# lcd.net
KiCad netlist of a schematic drawn in Altium Designer
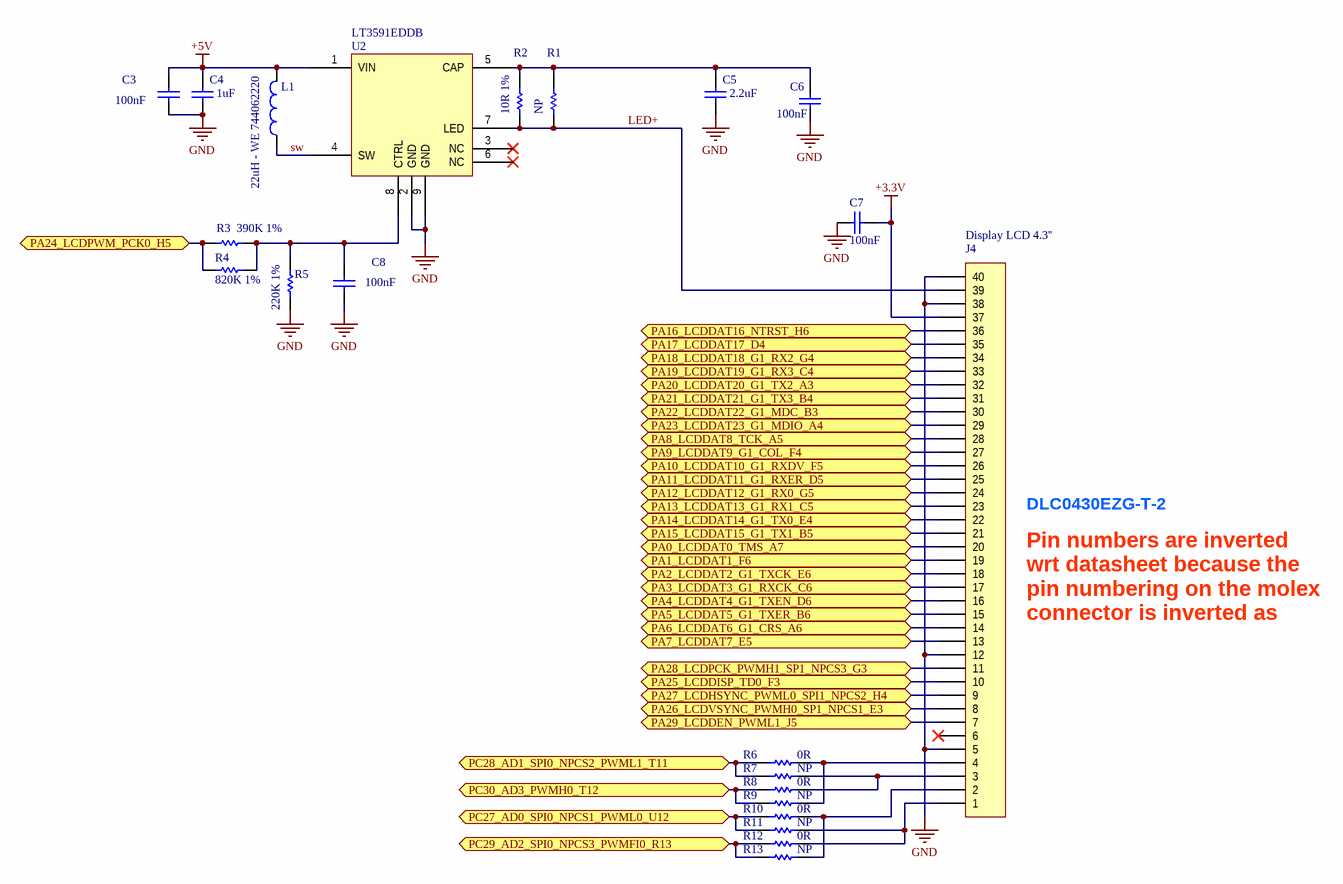
[diagram p0: lcd.SchDoc]

(export (version "E")
  (design (tool "Eeschema 10.0.6"))
  (components
    (comp (ref "C3")
      (value "100nF")
      (footprint "0603_[1608]")
      (description "Ceramic X7R 50V")
      (fields (field (name "PUBLISHER") "Altium Limited"))
      (libsource (lib "project42_lib") (part "Cap"))
    )
    (comp (ref "C4")
      (value "1uF")
      (footprint "0603_[1608]")
      (description "Ceramic X7R, X5R 16V")
      (fields (field (name "PUBLISHER") "Altium Limited"))
      (libsource (lib "project42_lib") (part "Cap"))
    )
    (comp (ref "C5")
      (value "2.2uF")
      (footprint "1210_[3225]")
      (description "Ceramic X7R, X5R 50V")
      (fields (field (name "PUBLISHER") "Altium Limited"))
      (libsource (lib "project42_lib") (part "Cap"))
    )
    (comp (ref "C6")
      (value "100nF")
      (footprint "0603_[1608]")
      (description "Ceramic X7R 50V")
      (fields (field (name "PUBLISHER") "Altium Limited"))
      (libsource (lib "project42_lib") (part "Cap"))
    )
    (comp (ref "C7")
      (value "100nF")
      (footprint "0603_[1608]")
      (description "Ceramic X5R 6.3V, 10V")
      (fields (field (name "PUBLISHER") "Altium Limited"))
      (libsource (lib "project42_lib") (part "Cap"))
    )
    (comp (ref "C8")
      (value "100nF")
      (footprint "0603_[1608]")
      (description "Ceramic X7R 50V")
      (fields (field (name "PUBLISHER") "Altium Limited"))
      (libsource (lib "project42_lib") (part "Cap"))
    )
    (comp (ref "J4")
      (value "Display LCD 4.3''")
      (footprint "fcc-zif_40pin_0.5mm")
      (description "40-pin, 0.5mm, SMT, ZIF, Horizontal, Top Contact (WE 68714014022; Molex: 54104-4031)")
      (fields (field (name "PUBLISHER") "Altium Limited"))
      (libsource (lib "DEVELER_Library") (part "Header 40"))
    )
    (comp (ref "L1")
      (value "22uH - WE 744062220")
      (footprint "WE-TPC-6823-X")
      (description "Power Inductor")
      (libsource (lib "DEVELER_Library") (part "Inductor"))
    )
    (comp (ref "R1")
      (value "NP")
      (footprint "0603_[1608]")
      (description "Resistor 0.125W")
      (fields (field (name "PUBLISHER") "Altium Limited"))
      (libsource (lib "project42_lib") (part "Res1"))
    )
    (comp (ref "R2")
      (value "10R 1%")
      (footprint "0603_[1608]")
      (description "Resistor 0.125W")
      (fields (field (name "PUBLISHER") "Altium Limited"))
      (libsource (lib "project42_lib") (part "Res1"))
    )
    (comp (ref "R3")
      (value "390K 1%")
      (footprint "0603_[1608]")
      (description "Resistor")
      (fields (field (name "PUBLISHER") "Altium Limited"))
      (libsource (lib "project42_lib") (part "Res1"))
    )
    (comp (ref "R4")
      (value "820K 1%")
      (footprint "0603_[1608]")
      (description "Resistor")
      (fields (field (name "PUBLISHER") "Altium Limited"))
      (libsource (lib "project42_lib") (part "Res1"))
    )
    (comp (ref "R5")
      (value "220K 1%")
      (footprint "0603_[1608]")
      (description "Resistor")
      (fields (field (name "PUBLISHER") "Altium Limited"))
      (libsource (lib "project42_lib") (part "Res1"))
    )
    (comp (ref "R6")
      (value "0R")
      (footprint "0603_[1608]")
      (description "Resistor")
      (fields (field (name "PUBLISHER") "Altium Limited"))
      (libsource (lib "project42_lib") (part "Res1"))
    )
    (comp (ref "R7")
      (value "NP")
      (footprint "0603_[1608]")
      (description "Resistor")
      (fields (field (name "PUBLISHER") "Altium Limited"))
      (libsource (lib "project42_lib") (part "Res1"))
    )
    (comp (ref "R8")
      (value "0R")
      (footprint "0603_[1608]")
      (description "Resistor")
      (fields (field (name "PUBLISHER") "Altium Limited"))
      (libsource (lib "project42_lib") (part "Res1"))
    )
    (comp (ref "R9")
      (value "NP")
      (footprint "0603_[1608]")
      (description "Resistor")
      (fields (field (name "PUBLISHER") "Altium Limited"))
      (libsource (lib "project42_lib") (part "Res1"))
    )
    (comp (ref "R10")
      (value "0R")
      (footprint "0603_[1608]")
      (description "Resistor")
      (fields (field (name "PUBLISHER") "Altium Limited"))
      (libsource (lib "project42_lib") (part "Res1"))
    )
    (comp (ref "R11")
      (value "NP")
      (footprint "0603_[1608]")
      (description "Resistor")
      (fields (field (name "PUBLISHER") "Altium Limited"))
      (libsource (lib "project42_lib") (part "Res1"))
    )
    (comp (ref "R12")
      (value "0R")
      (footprint "0603_[1608]")
      (description "Resistor")
      (fields (field (name "PUBLISHER") "Altium Limited"))
      (libsource (lib "project42_lib") (part "Res1"))
    )
    (comp (ref "R13")
      (value "NP")
      (footprint "0603_[1608]")
      (description "Resistor")
      (fields (field (name "PUBLISHER") "Altium Limited"))
      (libsource (lib "project42_lib") (part "Res1"))
    )
    (comp (ref "U2")
      (value "LT3591EDDB")
      (footprint "PQFN50P300X200X75_HS-9L")
      (description "White LED Driver with Integrated Schottky")
      (libsource (lib "DEVELER_Library") (part "LT3591"))
    )
  )
  (nets
    (net (code "1") (name "+3.3V") (class "Default")
      (node (ref "C7") (pin "1") (pinfunction "1_1") (pintype "passive"))
      (node (ref "J4") (pin "37") (pinfunction "37_37") (pintype "passive"))
    )
    (net (code "2") (name "+5V") (class "Default")
      (node (ref "C3") (pin "2") (pinfunction "2_2") (pintype "passive"))
      (node (ref "C4") (pin "2") (pinfunction "2_2") (pintype "passive"))
      (node (ref "L1") (pin "2") (pinfunction "2_2") (pintype "passive"))
      (node (ref "U2") (pin "1") (pinfunction "VIN_1") (pintype "power_in"))
    )
    (net (code "3") (name "/LED+") (class "Default")
      (node (ref "J4") (pin "39") (pinfunction "39_39") (pintype "passive"))
      (node (ref "R1") (pin "1") (pinfunction "1_1") (pintype "passive"))
      (node (ref "R2") (pin "1") (pinfunction "1_1") (pintype "passive"))
      (node (ref "U2") (pin "7") (pinfunction "LED_7") (pintype "passive"))
    )
    (net (code "4") (name "/PA0_LCDDAT0_TMS_A7") (class "Default")
      (node (ref "J4") (pin "20") (pinfunction "20_20") (pintype "passive"))
    )
    (net (code "5") (name "/PA1_LCDDAT1_F6") (class "Default")
      (node (ref "J4") (pin "19") (pinfunction "19_19") (pintype "passive"))
    )
    (net (code "6") (name "/PA2_LCDDAT2_G1_TXCK_E6") (class "Default")
      (node (ref "J4") (pin "18") (pinfunction "18_18") (pintype "passive"))
    )
    (net (code "7") (name "/PA3_LCDDAT3_G1_RXCK_C6") (class "Default")
      (node (ref "J4") (pin "17") (pinfunction "17_17") (pintype "passive"))
    )
    (net (code "8") (name "/PA4_LCDDAT4_G1_TXEN_D6") (class "Default")
      (node (ref "J4") (pin "16") (pinfunction "16_16") (pintype "passive"))
    )
    (net (code "9") (name "/PA5_LCDDAT5_G1_TXER_B6") (class "Default")
      (node (ref "J4") (pin "15") (pinfunction "15_15") (pintype "passive"))
    )
    (net (code "10") (name "/PA6_LCDDAT6_G1_CRS_A6") (class "Default")
      (node (ref "J4") (pin "14") (pinfunction "14_14") (pintype "passive"))
    )
    (net (code "11") (name "/PA7_LCDDAT7_E5") (class "Default")
      (node (ref "J4") (pin "13") (pinfunction "13_13") (pintype "passive"))
    )
    (net (code "12") (name "/PA8_LCDDAT8_TCK_A5") (class "Default")
      (node (ref "J4") (pin "28") (pinfunction "28_28") (pintype "passive"))
    )
    (net (code "13") (name "/PA9_LCDDAT9_G1_COL_F4") (class "Default")
      (node (ref "J4") (pin "27") (pinfunction "27_27") (pintype "passive"))
    )
    (net (code "14") (name "/PA10_LCDDAT10_G1_RXDV_F5") (class "Default")
      (node (ref "J4") (pin "26") (pinfunction "26_26") (pintype "passive"))
    )
    (net (code "15") (name "/PA11_LCDDAT11_G1_RXER_D5") (class "Default")
      (node (ref "J4") (pin "25") (pinfunction "25_25") (pintype "passive"))
    )
    (net (code "16") (name "/PA12_LCDDAT12_G1_RX0_G5") (class "Default")
      (node (ref "J4") (pin "24") (pinfunction "24_24") (pintype "passive"))
    )
    (net (code "17") (name "/PA13_LCDDAT13_G1_RX1_C5") (class "Default")
      (node (ref "J4") (pin "23") (pinfunction "23_23") (pintype "passive"))
    )
    (net (code "18") (name "/PA14_LCDDAT14_G1_TX0_E4") (class "Default")
      (node (ref "J4") (pin "22") (pinfunction "22_22") (pintype "passive"))
    )
    (net (code "19") (name "/PA15_LCDDAT15_G1_TX1_B5") (class "Default")
      (node (ref "J4") (pin "21") (pinfunction "21_21") (pintype "passive"))
    )
    (net (code "20") (name "/PA16_LCDDAT16_NTRST_H6") (class "Default")
      (node (ref "J4") (pin "36") (pinfunction "36_36") (pintype "passive"))
    )
    (net (code "21") (name "/PA17_LCDDAT17_D4") (class "Default")
      (node (ref "J4") (pin "35") (pinfunction "35_35") (pintype "passive"))
    )
    (net (code "22") (name "/PA18_LCDDAT18_G1_RX2_G4") (class "Default")
      (node (ref "J4") (pin "34") (pinfunction "34_34") (pintype "passive"))
    )
    (net (code "23") (name "/PA19_LCDDAT19_G1_RX3_C4") (class "Default")
      (node (ref "J4") (pin "33") (pinfunction "33_33") (pintype "passive"))
    )
    (net (code "24") (name "/PA20_LCDDAT20_G1_TX2_A3") (class "Default")
      (node (ref "J4") (pin "32") (pinfunction "32_32") (pintype "passive"))
    )
    (net (code "25") (name "/PA21_LCDDAT21_G1_TX3_B4") (class "Default")
      (node (ref "J4") (pin "31") (pinfunction "31_31") (pintype "passive"))
    )
    (net (code "26") (name "/PA22_LCDDAT22_G1_MDC_B3") (class "Default")
      (node (ref "J4") (pin "30") (pinfunction "30_30") (pintype "passive"))
    )
    (net (code "27") (name "/PA23_LCDDAT23_G1_MDIO_A4") (class "Default")
      (node (ref "J4") (pin "29") (pinfunction "29_29") (pintype "passive"))
    )
    (net (code "28") (name "/PA24_LCDPWM_PCK0_H5") (class "Default")
      (node (ref "R3") (pin "2") (pinfunction "2_2") (pintype "passive"))
      (node (ref "R4") (pin "1") (pinfunction "1_1") (pintype "passive"))
    )
    (net (code "29") (name "/PA25_LCDDISP_TD0_F3") (class "Default")
      (node (ref "J4") (pin "10") (pinfunction "10_10") (pintype "passive"))
    )
    (net (code "30") (name "/PA26_LCDVSYNC_PWMH0_SP1_NPCS1_E3") (class "Default")
      (node (ref "J4") (pin "8") (pinfunction "8_8") (pintype "passive"))
    )
    (net (code "31") (name "/PA27_LCDHSYNC_PWML0_SPI1_NPCS2_H4") (class "Default")
      (node (ref "J4") (pin "9") (pinfunction "9_9") (pintype "passive"))
    )
    (net (code "32") (name "/PA28_LCDPCK_PWMH1_SP1_NPCS3_G3") (class "Default")
      (node (ref "J4") (pin "11") (pinfunction "11_11") (pintype "passive"))
    )
    (net (code "33") (name "/PA29_LCDDEN_PWML1_J5") (class "Default")
      (node (ref "J4") (pin "7") (pinfunction "7_7") (pintype "passive"))
    )
    (net (code "34") (name "/PC27_AD0_SPI0_NPCS1_PWML0_U12") (class "Default")
      (node (ref "R10") (pin "2") (pinfunction "2_2") (pintype "passive"))
      (node (ref "R11") (pin "2") (pinfunction "2_2") (pintype "passive"))
    )
    (net (code "35") (name "/PC28_AD1_SPI0_NPCS2_PWML1_T11") (class "Default")
      (node (ref "R6") (pin "2") (pinfunction "2_2") (pintype "passive"))
      (node (ref "R7") (pin "2") (pinfunction "2_2") (pintype "passive"))
    )
    (net (code "36") (name "/PC29_AD2_SPI0_NPCS3_PWMFI0_R13") (class "Default")
      (node (ref "R12") (pin "2") (pinfunction "2_2") (pintype "passive"))
      (node (ref "R13") (pin "2") (pinfunction "2_2") (pintype "passive"))
    )
    (net (code "37") (name "/PC30_AD3_PWMH0_T12") (class "Default")
      (node (ref "R8") (pin "2") (pinfunction "2_2") (pintype "passive"))
      (node (ref "R9") (pin "2") (pinfunction "2_2") (pintype "passive"))
    )
    (net (code "38") (name "/sw") (class "Default")
      (node (ref "L1") (pin "1") (pinfunction "1_1") (pintype "passive"))
      (node (ref "U2") (pin "4") (pinfunction "SW_4") (pintype "passive"))
    )
    (net (code "39") (name "GND") (class "Default")
      (node (ref "C3") (pin "1") (pinfunction "1_1") (pintype "passive"))
      (node (ref "C4") (pin "1") (pinfunction "1_1") (pintype "passive"))
      (node (ref "C5") (pin "1") (pinfunction "1_1") (pintype "passive"))
      (node (ref "C6") (pin "1") (pinfunction "1_1") (pintype "passive"))
      (node (ref "C7") (pin "2") (pinfunction "2_2") (pintype "passive"))
      (node (ref "C8") (pin "1") (pinfunction "1_1") (pintype "passive"))
      (node (ref "J4") (pin "12") (pinfunction "12_12") (pintype "passive"))
      (node (ref "J4") (pin "38") (pinfunction "38_38") (pintype "passive"))
      (node (ref "J4") (pin "40") (pinfunction "40_40") (pintype "passive"))
      (node (ref "J4") (pin "5") (pinfunction "5_5") (pintype "passive"))
      (node (ref "R5") (pin "2") (pinfunction "2_2") (pintype "passive"))
      (node (ref "U2") (pin "2") (pinfunction "GND_2") (pintype "power_in"))
      (node (ref "U2") (pin "9") (pinfunction "GND_9") (pintype "power_in"))
    )
    (net (code "40") (name "Net-(J4-Pad1)") (class "Default")
      (node (ref "J4") (pin "1") (pinfunction "1_1") (pintype "passive"))
      (node (ref "R11") (pin "1") (pinfunction "1_1") (pintype "passive"))
      (node (ref "R12") (pin "1") (pinfunction "1_1") (pintype "passive"))
    )
    (net (code "41") (name "Net-(J4-Pad2)") (class "Default")
      (node (ref "J4") (pin "2") (pinfunction "2_2") (pintype "passive"))
      (node (ref "R10") (pin "1") (pinfunction "1_1") (pintype "passive"))
      (node (ref "R13") (pin "1") (pinfunction "1_1") (pintype "passive"))
    )
    (net (code "42") (name "Net-(J4-Pad3)") (class "Default")
      (node (ref "J4") (pin "3") (pinfunction "3_3") (pintype "passive"))
      (node (ref "R7") (pin "1") (pinfunction "1_1") (pintype "passive"))
      (node (ref "R8") (pin "1") (pinfunction "1_1") (pintype "passive"))
    )
    (net (code "43") (name "Net-(J4-Pad4)") (class "Default")
      (node (ref "J4") (pin "4") (pinfunction "4_4") (pintype "passive"))
      (node (ref "R6") (pin "1") (pinfunction "1_1") (pintype "passive"))
      (node (ref "R9") (pin "1") (pinfunction "1_1") (pintype "passive"))
    )
    (net (code "44") (name "Net-(U2-CAP)") (class "Default")
      (node (ref "C5") (pin "2") (pinfunction "2_2") (pintype "passive"))
      (node (ref "C6") (pin "2") (pinfunction "2_2") (pintype "passive"))
      (node (ref "R1") (pin "2") (pinfunction "2_2") (pintype "passive"))
      (node (ref "R2") (pin "2") (pinfunction "2_2") (pintype "passive"))
      (node (ref "U2") (pin "5") (pinfunction "CAP_5") (pintype "passive"))
    )
    (net (code "45") (name "Net-(U2-CTRL)") (class "Default")
      (node (ref "C8") (pin "2") (pinfunction "2_2") (pintype "passive"))
      (node (ref "R3") (pin "1") (pinfunction "1_1") (pintype "passive"))
      (node (ref "R4") (pin "2") (pinfunction "2_2") (pintype "passive"))
      (node (ref "R5") (pin "1") (pinfunction "1_1") (pintype "passive"))
      (node (ref "U2") (pin "8") (pinfunction "CTRL_8") (pintype "passive"))
    )
    (net (code "46") (name "unconnected-(J4-Pad6)") (class "Default")
      (node (ref "J4") (pin "6") (pinfunction "6_6") (pintype "passive+no_connect"))
    )
    (net (code "47") (name "unconnected-(U2-NC-Pad3)") (class "Default")
      (node (ref "U2") (pin "3") (pinfunction "NC_3") (pintype "passive+no_connect"))
    )
    (net (code "48") (name "unconnected-(U2-NC-Pad6)") (class "Default")
      (node (ref "U2") (pin "6") (pinfunction "NC_6") (pintype "passive+no_connect"))
    )
  )
)
